# Addon-mapleCUx_HM-RFM69-RFM95-V15-003-TX.net
KiCad netlist of a schematic drawn in EAGLE
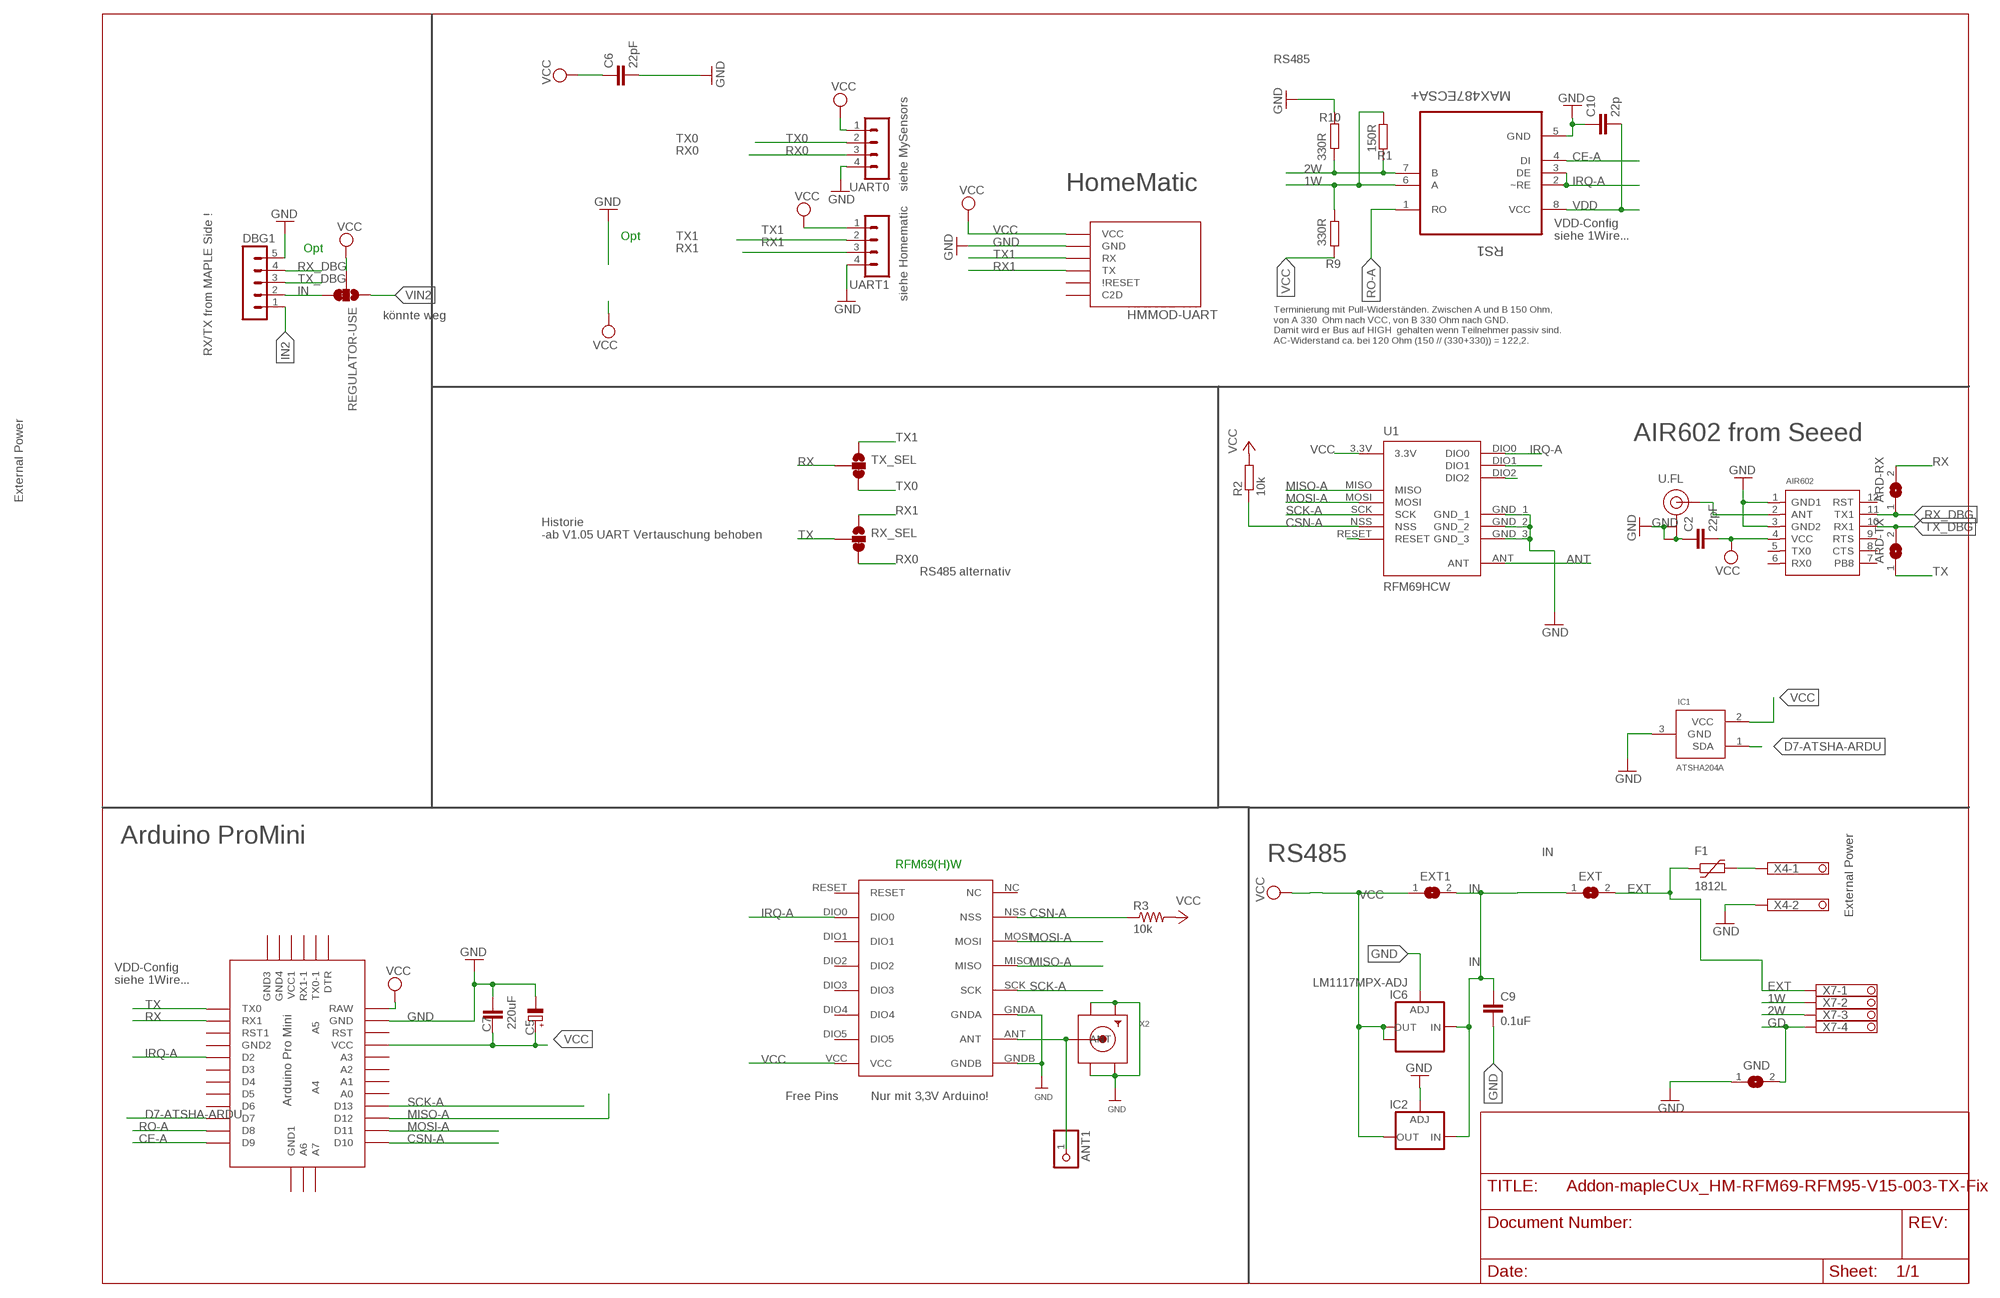
[diagram p0: schematic, sheet 1]

(export (version "E")
  (design (tool "Eeschema 10.0.6"))
  (components
    (comp (ref "AIR602")
      (value "AIR602")
      (footprint "eagle-import:MODULE12P-2.0-10X12MM")
      (libsource (lib "eagle-import") (part "AIR602"))
    )
    (comp (ref "ANT1")
      (value "PINHD-1X1")
      (footprint "eagle-import:1X01")
      (libsource (lib "eagle-import") (part "PINHD-1X1"))
    )
    (comp (ref "ARD-RX")
      (value "SJ")
      (footprint "eagle-import:SJ")
      (libsource (lib "eagle-import") (part "SJ"))
    )
    (comp (ref "ARD-TX")
      (value "SJ")
      (footprint "eagle-import:SJ")
      (libsource (lib "eagle-import") (part "SJ"))
    )
    (comp (ref "C2")
      (value "22pF")
      (footprint "eagle-import:C0805")
      (libsource (lib "eagle-import") (part "C-EUC0805"))
    )
    (comp (ref "C5")
      (value "220uF")
      (footprint "eagle-import:E5-8,5")
      (libsource (lib "eagle-import") (part "CPOL-EUE5-8.5"))
    )
    (comp (ref "C6")
      (value "22pF")
      (footprint "eagle-import:C0805")
      (libsource (lib "eagle-import") (part "C-EUC0805"))
    )
    (comp (ref "C7")
      (value "C-EUC1812")
      (footprint "eagle-import:C1812")
      (libsource (lib "eagle-import") (part "C-EUC1812"))
    )
    (comp (ref "C9")
      (value "0.1uF")
      (footprint "eagle-import:C1206")
      (libsource (lib "eagle-import") (part "C-EUC1206"))
    )
    (comp (ref "C10")
      (value "22p")
      (footprint "eagle-import:C0805")
      (libsource (lib "eagle-import") (part "C-EUC0805"))
    )
    (comp (ref "DBG1")
      (value "MA05-1")
      (footprint "eagle-import:MA05-1")
      (libsource (lib "eagle-import") (part "MA05-1"))
    )
    (comp (ref "EXT") (value "SJ") (footprint "eagle-import:SJ") (libsource (lib "eagle-import") (part "SJ")))
    (comp (ref "EXT1")
      (value "SJ")
      (footprint "eagle-import:SJ")
      (libsource (lib "eagle-import") (part "SJ"))
    )
    (comp (ref "F1")
      (value "1812L")
      (footprint "eagle-import:1812L")
      (libsource (lib "eagle-import") (part "1812L"))
    )
    (comp (ref "GND") (value "SJ") (footprint "eagle-import:SJ") (libsource (lib "eagle-import") (part "SJ")))
    (comp (ref "HMMOD-UART")
      (value "HM-MOD-UARTDIL")
      (footprint "eagle-import:HM-MOD-UART-DIL")
      (libsource (lib "eagle-import") (part "HM-MOD-UARTDIL"))
    )
    (comp (ref "IC1")
      (value "ATSHA204A")
      (footprint "eagle-import:SOT23")
      (libsource (lib "eagle-import") (part "ATSHA204A"))
    )
    (comp (ref "IC2")
      (value "LD117ADT50TR")
      (footprint "eagle-import:DPACK")
      (libsource (lib "eagle-import") (part "LD117A?DT50TR"))
    )
    (comp (ref "IC6")
      (value "LM1117MPX-ADJ")
      (footprint "eagle-import:SOT223")
      (libsource (lib "eagle-import") (part "LM1117MPX-ADJ"))
    )
    (comp (ref "R1")
      (value "150R")
      (footprint "eagle-import:R0805")
      (libsource (lib "eagle-import") (part "R-EU_R0805"))
    )
    (comp (ref "R2")
      (value "10k")
      (footprint "eagle-import:M0805")
      (libsource (lib "eagle-import") (part "R-EU_M0805"))
    )
    (comp (ref "R3")
      (value "10k")
      (footprint "eagle-import:0805")
      (libsource (lib "eagle-import") (part "RESISTOR0805-RES"))
    )
    (comp (ref "R9")
      (value "330R")
      (footprint "eagle-import:R0805")
      (libsource (lib "eagle-import") (part "R-EU_R0805"))
    )
    (comp (ref "R10")
      (value "330R")
      (footprint "eagle-import:R0805")
      (libsource (lib "eagle-import") (part "R-EU_R0805"))
    )
    (comp (ref "REGULATOR-USE")
      (value "JUMPER-SMT_3_1-NC_TRACE_SILK")
      (footprint "eagle-import:SMT-JUMPER_3_1-NC_TRACE_SILK")
      (libsource (lib "eagle-import") (part "JUMPER-SMT_3_1-NC_TRACE_SILK"))
    )
    (comp (ref "RFM69W")
      (value "RFM69HW")
      (footprint "eagle-import:RFM")
      (libsource (lib "eagle-import") (part "RFM69HW"))
    )
    (comp (ref "RS1")
      (value "MAX487ECSA+")
      (footprint "eagle-import:SOIC127P600X175-8N")
      (libsource (lib "eagle-import") (part "MAX487ECSA+"))
    )
    (comp (ref "RX_SEL")
      (value "JUMPER-SMT_3_1-NC_TRACE_SILK")
      (footprint "eagle-import:SMT-JUMPER_3_1-NC_TRACE_SILK")
      (libsource (lib "eagle-import") (part "JUMPER-SMT_3_1-NC_TRACE_SILK"))
    )
    (comp (ref "TX_SEL")
      (value "JUMPER-SMT_3_1-NC_TRACE_SILK")
      (footprint "eagle-import:SMT-JUMPER_3_1-NC_TRACE_SILK")
      (libsource (lib "eagle-import") (part "JUMPER-SMT_3_1-NC_TRACE_SILK"))
    )
    (comp (ref "U$2")
      (value "ABK-PRO-MINI")
      (footprint "eagle-import:ABK-PRO-MINI")
      (libsource (lib "eagle-import") (part "ABK-PRO-MINI"))
    )
    (comp (ref "U.FL")
      (value "U.FL")
      (footprint "eagle-import:U.FL")
      (libsource (lib "eagle-import") (part "U.FL"))
    )
    (comp (ref "U1")
      (value "RFM69HCW")
      (footprint "eagle-import:RFM69HCW-XXXS2")
      (libsource (lib "eagle-import") (part "RFM69HCW"))
    )
    (comp (ref "UART0")
      (value "MA04-1")
      (footprint "eagle-import:MA04-1")
      (libsource (lib "eagle-import") (part "MA04-1"))
    )
    (comp (ref "UART1")
      (value "MA04-1")
      (footprint "eagle-import:MA04-1")
      (libsource (lib "eagle-import") (part "MA04-1"))
    )
    (comp (ref "X2")
      (value "SMACONNECTOR_EDGE")
      (footprint "eagle-import:SMA_EDGELAUNCH")
      (libsource (lib "eagle-import") (part "SMACONNECTOR_EDGE"))
    )
    (comp (ref "X4")
      (value "1751248")
      (footprint "eagle-import:1751248")
      (libsource (lib "eagle-import") (part "1751248"))
    )
    (comp (ref "X7")
      (value "1751264")
      (footprint "eagle-import:1751264")
      (libsource (lib "eagle-import") (part "1751264"))
    )
  )
  (nets
    (net (code "1") (name "/1W") (class "Default")
      (node (ref "R1") (pin "1") (pinfunction "1_1") (pintype "passive"))
      (node (ref "R9") (pin "2") (pinfunction "2_2") (pintype "passive"))
      (node (ref "RS1") (pin "6") (pinfunction "A_6") (pintype "bidirectional"))
      (node (ref "X7") (pin "2") (pinfunction "K_2") (pintype "passive"))
    )
    (net (code "2") (name "/2W") (class "Default")
      (node (ref "R1") (pin "2") (pinfunction "2_2") (pintype "passive"))
      (node (ref "R10") (pin "1") (pinfunction "1_1") (pintype "passive"))
      (node (ref "RS1") (pin "7") (pinfunction "B_7") (pintype "bidirectional"))
      (node (ref "X7") (pin "3") (pinfunction "K_3") (pintype "passive"))
    )
    (net (code "3") (name "/ANT") (class "Default")
      (node (ref "ANT1") (pin "1") (pinfunction "1_1") (pintype "passive"))
      (node (ref "RFM69W") (pin "ANT") (pinfunction "ANT_ANT") (pintype "bidirectional"))
      (node (ref "U1") (pin "ANT") (pinfunction "ANT_ANT") (pintype "passive"))
      (node (ref "X2") (pin "P") (pinfunction "ANT_P") (pintype "bidirectional"))
    )
    (net (code "4") (name "/CE-A") (class "Default")
      (node (ref "RS1") (pin "4") (pinfunction "DI_4") (pintype "input"))
      (node (ref "U$2") (pin "D9") (pinfunction "D9_D9") (pintype "bidirectional"))
    )
    (net (code "5") (name "/CSN-A") (class "Default")
      (node (ref "R2") (pin "1") (pinfunction "1_1") (pintype "passive"))
      (node (ref "R3") (pin "1") (pinfunction "1_1") (pintype "passive"))
      (node (ref "RFM69W") (pin "NSS") (pinfunction "NSS_NSS") (pintype "bidirectional"))
      (node (ref "U$2") (pin "D10") (pinfunction "D10_D10") (pintype "bidirectional"))
      (node (ref "U1") (pin "NSS") (pinfunction "NSS_NSS") (pintype "input"))
    )
    (net (code "6") (name "/EXT") (class "Default")
      (node (ref "EXT") (pin "2") (pinfunction "2_2") (pintype "passive"))
      (node (ref "F1") (pin "P$1") (pinfunction "1_P$1") (pintype "passive"))
      (node (ref "X7") (pin "1") (pinfunction "K_1") (pintype "passive"))
    )
    (net (code "7") (name "/GD") (class "Default")
      (node (ref "GND") (pin "2") (pinfunction "2_2") (pintype "passive"))
      (node (ref "X7") (pin "4") (pinfunction "K_4") (pintype "passive"))
    )
    (net (code "8") (name "/IN") (class "Default")
      (node (ref "C9") (pin "1") (pinfunction "1_1") (pintype "passive"))
      (node (ref "DBG1") (pin "2") (pinfunction "2_2") (pintype "passive"))
      (node (ref "EXT") (pin "1") (pinfunction "1_1") (pintype "passive"))
      (node (ref "EXT1") (pin "2") (pinfunction "2_2") (pintype "passive"))
      (node (ref "IC2") (pin "3") (pinfunction "IN_3") (pintype "input"))
      (node (ref "IC6") (pin "3") (pinfunction "IN_3") (pintype "input"))
      (node (ref "REGULATOR-USE") (pin "3") (pinfunction "3_3") (pintype "passive"))
    )
    (net (code "9") (name "/IRQ-A") (class "Default")
      (node (ref "RFM69W") (pin "DIO0") (pinfunction "DIO0_DIO0") (pintype "bidirectional"))
      (node (ref "RS1") (pin "2") (pinfunction "~{RE}_2") (pintype "input"))
      (node (ref "RS1") (pin "3") (pinfunction "DE_3") (pintype "input"))
      (node (ref "U$2") (pin "D2") (pinfunction "D2_D2") (pintype "bidirectional"))
      (node (ref "U1") (pin "DIO0") (pinfunction "DIO0_DIO0") (pintype "bidirectional"))
    )
    (net (code "10") (name "/MISO-A") (class "Default")
      (node (ref "RFM69W") (pin "MISO") (pinfunction "MISO_MISO") (pintype "bidirectional"))
      (node (ref "U$2") (pin "D12") (pinfunction "D12_D12") (pintype "bidirectional"))
      (node (ref "U1") (pin "MISO") (pinfunction "MISO_MISO") (pintype "bidirectional"))
    )
    (net (code "11") (name "/MOSI-A") (class "Default")
      (node (ref "RFM69W") (pin "MOSI") (pinfunction "MOSI_MOSI") (pintype "bidirectional"))
      (node (ref "U$2") (pin "D11") (pinfunction "D11_D11") (pintype "bidirectional"))
      (node (ref "U1") (pin "MOSI") (pinfunction "MOSI_MOSI") (pintype "input"))
    )
    (net (code "12") (name "/RX") (class "Default")
      (node (ref "ARD-RX") (pin "2") (pinfunction "2_2") (pintype "passive"))
      (node (ref "TX_SEL") (pin "2") (pinfunction "2_2") (pintype "passive"))
      (node (ref "U$2") (pin "RX1") (pinfunction "RX1_RX1") (pintype "bidirectional"))
    )
    (net (code "13") (name "/RX0") (class "Default")
      (node (ref "RX_SEL") (pin "3") (pinfunction "3_3") (pintype "passive"))
      (node (ref "UART0") (pin "3") (pinfunction "3_3") (pintype "passive"))
    )
    (net (code "14") (name "/RX1") (class "Default")
      (node (ref "HMMOD-UART") (pin "5") (pinfunction "TX_5") (pintype "bidirectional"))
      (node (ref "RX_SEL") (pin "1") (pinfunction "1_1") (pintype "passive"))
      (node (ref "UART1") (pin "3") (pinfunction "3_3") (pintype "passive"))
    )
    (net (code "15") (name "/SCK-A") (class "Default")
      (node (ref "RFM69W") (pin "SCK") (pinfunction "SCK_SCK") (pintype "bidirectional"))
      (node (ref "U$2") (pin "D13") (pinfunction "D13_D13") (pintype "bidirectional"))
      (node (ref "U1") (pin "SCK") (pinfunction "SCK_SCK") (pintype "input"))
    )
    (net (code "16") (name "/TX") (class "Default")
      (node (ref "ARD-TX") (pin "1") (pinfunction "1_1") (pintype "passive"))
      (node (ref "RX_SEL") (pin "2") (pinfunction "2_2") (pintype "passive"))
      (node (ref "U$2") (pin "TX0") (pinfunction "TX0_TX0") (pintype "bidirectional"))
    )
    (net (code "17") (name "/TX0") (class "Default")
      (node (ref "TX_SEL") (pin "3") (pinfunction "3_3") (pintype "passive"))
      (node (ref "UART0") (pin "2") (pinfunction "2_2") (pintype "passive"))
    )
    (net (code "18") (name "/TX1") (class "Default")
      (node (ref "HMMOD-UART") (pin "6") (pinfunction "RX_6") (pintype "bidirectional"))
      (node (ref "TX_SEL") (pin "1") (pinfunction "1_1") (pintype "passive"))
      (node (ref "UART1") (pin "2") (pinfunction "2_2") (pintype "passive"))
    )
    (net (code "19") (name "/VDD") (class "Default")
      (node (ref "C10") (pin "2") (pinfunction "2_2") (pintype "passive"))
      (node (ref "RS1") (pin "8") (pinfunction "VCC_8") (pintype "power_in"))
    )
    (net (code "20") (name "D7-ATSHA-ARDU") (class "Default")
      (node (ref "IC1") (pin "1") (pinfunction "SDA_1") (pintype "bidirectional"))
      (node (ref "U$2") (pin "D7") (pinfunction "D7_D7") (pintype "bidirectional"))
    )
    (net (code "21") (name "GND") (class "Default")
      (node (ref "AIR602") (pin "1") (pinfunction "GND1_1") (pintype "bidirectional"))
      (node (ref "AIR602") (pin "3") (pinfunction "GND2_3") (pintype "bidirectional"))
      (node (ref "C10") (pin "1") (pinfunction "1_1") (pintype "passive"))
      (node (ref "C2") (pin "1") (pinfunction "1_1") (pintype "passive"))
      (node (ref "C5") (pin "-") (pinfunction "-_-") (pintype "passive"))
      (node (ref "C6") (pin "2") (pinfunction "2_2") (pintype "passive"))
      (node (ref "C7") (pin "1") (pinfunction "1_1") (pintype "passive"))
      (node (ref "C9") (pin "2") (pinfunction "2_2") (pintype "passive"))
      (node (ref "DBG1") (pin "5") (pinfunction "5_5") (pintype "passive"))
      (node (ref "GND") (pin "1") (pinfunction "1_1") (pintype "passive"))
      (node (ref "HMMOD-UART") (pin "2") (pinfunction "GND_2") (pintype "power_in"))
      (node (ref "IC1") (pin "3") (pinfunction "GND_3") (pintype "bidirectional"))
      (node (ref "IC2") (pin "1") (pinfunction "ADJ_1") (pintype "input"))
      (node (ref "IC6") (pin "1") (pinfunction "ADJ_1") (pintype "input"))
      (node (ref "R10") (pin "2") (pinfunction "2_2") (pintype "passive"))
      (node (ref "RFM69W") (pin "GNDA") (pinfunction "GNDA_GNDA") (pintype "bidirectional"))
      (node (ref "RFM69W") (pin "GNDB") (pinfunction "GNDB_GNDB") (pintype "bidirectional"))
      (node (ref "RS1") (pin "5") (pinfunction "GND_5") (pintype "passive"))
      (node (ref "U$2") (pin "GND") (pinfunction "GND_GND") (pintype "bidirectional"))
      (node (ref "U.FL") (pin "1") (pinfunction "GND_1") (pintype "bidirectional"))
      (node (ref "U.FL") (pin "2") (pinfunction "GND_2") (pintype "bidirectional"))
      (node (ref "U1") (pin "GND_1") (pinfunction "GND_1_GND_1") (pintype "power_in"))
      (node (ref "U1") (pin "GND_2") (pinfunction "GND_2_GND_2") (pintype "power_in"))
      (node (ref "U1") (pin "GND_3") (pinfunction "GND_3_GND_3") (pintype "power_in"))
      (node (ref "UART0") (pin "4") (pinfunction "4_4") (pintype "passive"))
      (node (ref "UART1") (pin "4") (pinfunction "4_4") (pintype "passive"))
      (node (ref "X2") (pin "GND@1") (pinfunction "GND4_GND@1") (pintype "power_in"))
      (node (ref "X2") (pin "GND@2") (pinfunction "GND3_GND@2") (pintype "power_in"))
      (node (ref "X2") (pin "GND@3") (pinfunction "GND2_GND@3") (pintype "power_in"))
      (node (ref "X2") (pin "GND@4") (pinfunction "GND1_GND@4") (pintype "power_in"))
      (node (ref "X4") (pin "2") (pinfunction "K_2") (pintype "passive"))
    )
    (net (code "22") (name "IN2") (class "Default")
      (node (ref "DBG1") (pin "1") (pinfunction "1_1") (pintype "passive"))
    )
    (net (code "23") (name "Net-(AIR602-ANT)") (class "Default")
      (node (ref "AIR602") (pin "2") (pinfunction "ANT_2") (pintype "bidirectional"))
      (node (ref "U.FL") (pin "FEED") (pinfunction "SIGNAL_FEED") (pintype "bidirectional"))
    )
    (net (code "24") (name "Net-(F1-2)") (class "Default")
      (node (ref "F1") (pin "P$2") (pinfunction "2_P$2") (pintype "passive"))
      (node (ref "X4") (pin "1") (pinfunction "K_1") (pintype "passive"))
    )
    (net (code "25") (name "RO-A") (class "Default")
      (node (ref "RS1") (pin "1") (pinfunction "RO_1") (pintype "output"))
      (node (ref "U$2") (pin "D8") (pinfunction "D8_D8") (pintype "bidirectional"))
    )
    (net (code "26") (name "RX_DBG") (class "Default")
      (node (ref "AIR602") (pin "11") (pinfunction "TX1_11") (pintype "bidirectional"))
      (node (ref "ARD-RX") (pin "1") (pinfunction "1_1") (pintype "passive"))
      (node (ref "DBG1") (pin "4") (pinfunction "4_4") (pintype "passive"))
    )
    (net (code "27") (name "TX_DBG") (class "Default")
      (node (ref "AIR602") (pin "10") (pinfunction "RX1_10") (pintype "bidirectional"))
      (node (ref "ARD-TX") (pin "2") (pinfunction "2_2") (pintype "passive"))
      (node (ref "DBG1") (pin "3") (pinfunction "3_3") (pintype "passive"))
    )
    (net (code "28") (name "VCC") (class "Default")
      (node (ref "AIR602") (pin "4") (pinfunction "VCC_4") (pintype "bidirectional"))
      (node (ref "C2") (pin "2") (pinfunction "2_2") (pintype "passive"))
      (node (ref "C5") (pin "+") (pinfunction "+_+") (pintype "passive"))
      (node (ref "C6") (pin "1") (pinfunction "1_1") (pintype "passive"))
      (node (ref "C7") (pin "2") (pinfunction "2_2") (pintype "passive"))
      (node (ref "EXT1") (pin "1") (pinfunction "1_1") (pintype "passive"))
      (node (ref "HMMOD-UART") (pin "1") (pinfunction "VCC_1") (pintype "power_in"))
      (node (ref "IC1") (pin "2") (pinfunction "VCC_2") (pintype "bidirectional"))
      (node (ref "IC2") (pin "4") (pinfunction "OUT_4") (pintype "passive"))
      (node (ref "IC6") (pin "2") (pinfunction "OUT_2") (pintype "passive"))
      (node (ref "IC6") (pin "TAB") (pinfunction "OUT1_TAB") (pintype "passive"))
      (node (ref "R2") (pin "2") (pinfunction "2_2") (pintype "passive"))
      (node (ref "R3") (pin "2") (pinfunction "2_2") (pintype "passive"))
      (node (ref "R9") (pin "1") (pinfunction "1_1") (pintype "passive"))
      (node (ref "REGULATOR-USE") (pin "2") (pinfunction "2_2") (pintype "passive"))
      (node (ref "RFM69W") (pin "VCC") (pinfunction "VCC_VCC") (pintype "bidirectional"))
      (node (ref "U$2") (pin "RAW") (pinfunction "RAW_RAW") (pintype "bidirectional"))
      (node (ref "U$2") (pin "VCC") (pinfunction "VCC_VCC") (pintype "bidirectional"))
      (node (ref "U1") (pin "3.3V") (pinfunction "3.3V_3.3V") (pintype "power_in"))
      (node (ref "UART0") (pin "1") (pinfunction "1_1") (pintype "passive"))
      (node (ref "UART1") (pin "1") (pinfunction "1_1") (pintype "passive"))
    )
    (net (code "29") (name "VIN2") (class "Default")
      (node (ref "REGULATOR-USE") (pin "1") (pinfunction "1_1") (pintype "passive"))
    )
    (net (code "30") (name "unconnected-(AIR602-CTS-Pad8)") (class "Default")
      (node (ref "AIR602") (pin "8") (pinfunction "CTS_8") (pintype "bidirectional"))
    )
    (net (code "31") (name "unconnected-(AIR602-PB8-Pad7)") (class "Default")
      (node (ref "AIR602") (pin "7") (pinfunction "PB8_7") (pintype "bidirectional"))
    )
    (net (code "32") (name "unconnected-(AIR602-RST-Pad12)") (class "Default")
      (node (ref "AIR602") (pin "12") (pinfunction "RST_12") (pintype "bidirectional"))
    )
    (net (code "33") (name "unconnected-(AIR602-RTS-Pad9)") (class "Default")
      (node (ref "AIR602") (pin "9") (pinfunction "RTS_9") (pintype "bidirectional"))
    )
    (net (code "34") (name "unconnected-(AIR602-RX0-Pad6)") (class "Default")
      (node (ref "AIR602") (pin "6") (pinfunction "RX0_6") (pintype "bidirectional"))
    )
    (net (code "35") (name "unconnected-(AIR602-TX0-Pad5)") (class "Default")
      (node (ref "AIR602") (pin "5") (pinfunction "TX0_5") (pintype "bidirectional"))
    )
    (net (code "36") (name "unconnected-(HMMOD-UART-C2D-Pad3)") (class "Default")
      (node (ref "HMMOD-UART") (pin "3") (pinfunction "C2D_3") (pintype "bidirectional"))
    )
    (net (code "37") (name "unconnected-(HMMOD-UART-\\~{RESET}-Pad4)") (class "Default")
      (node (ref "HMMOD-UART") (pin "4") (pinfunction "\\~{RESET}_4") (pintype "bidirectional"))
    )
    (net (code "38") (name "unconnected-(RFM69W-PadDIO1)") (class "Default")
      (node (ref "RFM69W") (pin "DIO1") (pinfunction "DIO1_DIO1") (pintype "bidirectional"))
    )
    (net (code "39") (name "unconnected-(RFM69W-PadDIO2)") (class "Default")
      (node (ref "RFM69W") (pin "DIO2") (pinfunction "DIO2_DIO2") (pintype "bidirectional"))
    )
    (net (code "40") (name "unconnected-(RFM69W-PadDIO3)") (class "Default")
      (node (ref "RFM69W") (pin "DIO3") (pinfunction "DIO3_DIO3") (pintype "bidirectional"))
    )
    (net (code "41") (name "unconnected-(RFM69W-PadDIO4)") (class "Default")
      (node (ref "RFM69W") (pin "DIO4") (pinfunction "DIO4_DIO4") (pintype "bidirectional"))
    )
    (net (code "42") (name "unconnected-(RFM69W-PadDIO5)") (class "Default")
      (node (ref "RFM69W") (pin "DIO5") (pinfunction "DIO5_DIO5") (pintype "bidirectional"))
    )
    (net (code "43") (name "unconnected-(RFM69W-PadNC)") (class "Default")
      (node (ref "RFM69W") (pin "NC") (pinfunction "NC_NC") (pintype "bidirectional"))
    )
    (net (code "44") (name "unconnected-(RFM69W-PadRESET)") (class "Default")
      (node (ref "RFM69W") (pin "RESET") (pinfunction "RESET_RESET") (pintype "bidirectional"))
    )
    (net (code "45") (name "unconnected-(U$2-GND1-PadGND4)") (class "Default")
      (node (ref "U$2") (pin "GND4") (pinfunction "GND1_GND4") (pintype "bidirectional"))
    )
    (net (code "46") (name "unconnected-(U$2-GND2-PadGND1)") (class "Default")
      (node (ref "U$2") (pin "GND1") (pinfunction "GND2_GND1") (pintype "bidirectional"))
    )
    (net (code "47") (name "unconnected-(U$2-GND3-PadGND2)") (class "Default")
      (node (ref "U$2") (pin "GND2") (pinfunction "GND3_GND2") (pintype "bidirectional"))
    )
    (net (code "48") (name "unconnected-(U$2-GND4-PadGND3)") (class "Default")
      (node (ref "U$2") (pin "GND3") (pinfunction "GND4_GND3") (pintype "bidirectional"))
    )
    (net (code "49") (name "unconnected-(U$2-PadA0)") (class "Default")
      (node (ref "U$2") (pin "A0") (pinfunction "A0_A0") (pintype "bidirectional"))
    )
    (net (code "50") (name "unconnected-(U$2-PadA1)") (class "Default")
      (node (ref "U$2") (pin "A1") (pinfunction "A1_A1") (pintype "bidirectional"))
    )
    (net (code "51") (name "unconnected-(U$2-PadA2)") (class "Default")
      (node (ref "U$2") (pin "A2") (pinfunction "A2_A2") (pintype "bidirectional"))
    )
    (net (code "52") (name "unconnected-(U$2-PadA3)") (class "Default")
      (node (ref "U$2") (pin "A3") (pinfunction "A3_A3") (pintype "bidirectional"))
    )
    (net (code "53") (name "unconnected-(U$2-PadA4)") (class "Default")
      (node (ref "U$2") (pin "A4") (pinfunction "A4_A4") (pintype "bidirectional"))
    )
    (net (code "54") (name "unconnected-(U$2-PadA5)") (class "Default")
      (node (ref "U$2") (pin "A5") (pinfunction "A5_A5") (pintype "bidirectional"))
    )
    (net (code "55") (name "unconnected-(U$2-PadA6)") (class "Default")
      (node (ref "U$2") (pin "A6") (pinfunction "A6_A6") (pintype "bidirectional"))
    )
    (net (code "56") (name "unconnected-(U$2-PadA7)") (class "Default")
      (node (ref "U$2") (pin "A7") (pinfunction "A7_A7") (pintype "bidirectional"))
    )
    (net (code "57") (name "unconnected-(U$2-PadD3)") (class "Default")
      (node (ref "U$2") (pin "D3") (pinfunction "D3_D3") (pintype "bidirectional"))
    )
    (net (code "58") (name "unconnected-(U$2-PadD4)") (class "Default")
      (node (ref "U$2") (pin "D4") (pinfunction "D4_D4") (pintype "bidirectional"))
    )
    (net (code "59") (name "unconnected-(U$2-PadD5)") (class "Default")
      (node (ref "U$2") (pin "D5") (pinfunction "D5_D5") (pintype "bidirectional"))
    )
    (net (code "60") (name "unconnected-(U$2-PadD6)") (class "Default")
      (node (ref "U$2") (pin "D6") (pinfunction "D6_D6") (pintype "bidirectional"))
    )
    (net (code "61") (name "unconnected-(U$2-PadDTR)") (class "Default")
      (node (ref "U$2") (pin "DTR") (pinfunction "DTR_DTR") (pintype "bidirectional"))
    )
    (net (code "62") (name "unconnected-(U$2-PadRST)") (class "Default")
      (node (ref "U$2") (pin "RST") (pinfunction "RST_RST") (pintype "bidirectional"))
    )
    (net (code "63") (name "unconnected-(U$2-PadRST1)") (class "Default")
      (node (ref "U$2") (pin "RST1") (pinfunction "RST1_RST1") (pintype "bidirectional"))
    )
    (net (code "64") (name "unconnected-(U$2-PadRX1-1)") (class "Default")
      (node (ref "U$2") (pin "RX1-1") (pinfunction "RX1-1_RX1-1") (pintype "bidirectional"))
    )
    (net (code "65") (name "unconnected-(U$2-PadTX0-1)") (class "Default")
      (node (ref "U$2") (pin "TX0-1") (pinfunction "TX0-1_TX0-1") (pintype "bidirectional"))
    )
    (net (code "66") (name "unconnected-(U$2-PadVCC1)") (class "Default")
      (node (ref "U$2") (pin "VCC1") (pinfunction "VCC1_VCC1") (pintype "bidirectional"))
    )
    (net (code "67") (name "unconnected-(U1-PadDIO1)") (class "Default")
      (node (ref "U1") (pin "DIO1") (pinfunction "DIO1_DIO1") (pintype "bidirectional"))
    )
    (net (code "68") (name "unconnected-(U1-PadDIO2)") (class "Default")
      (node (ref "U1") (pin "DIO2") (pinfunction "DIO2_DIO2") (pintype "bidirectional"))
    )
    (net (code "69") (name "unconnected-(U1-PadRESET)") (class "Default")
      (node (ref "U1") (pin "RESET") (pinfunction "RESET_RESET") (pintype "input"))
    )
  )
)
